# LowPassFilter.net
KiCad netlist of a schematic drawn in Altium Designer
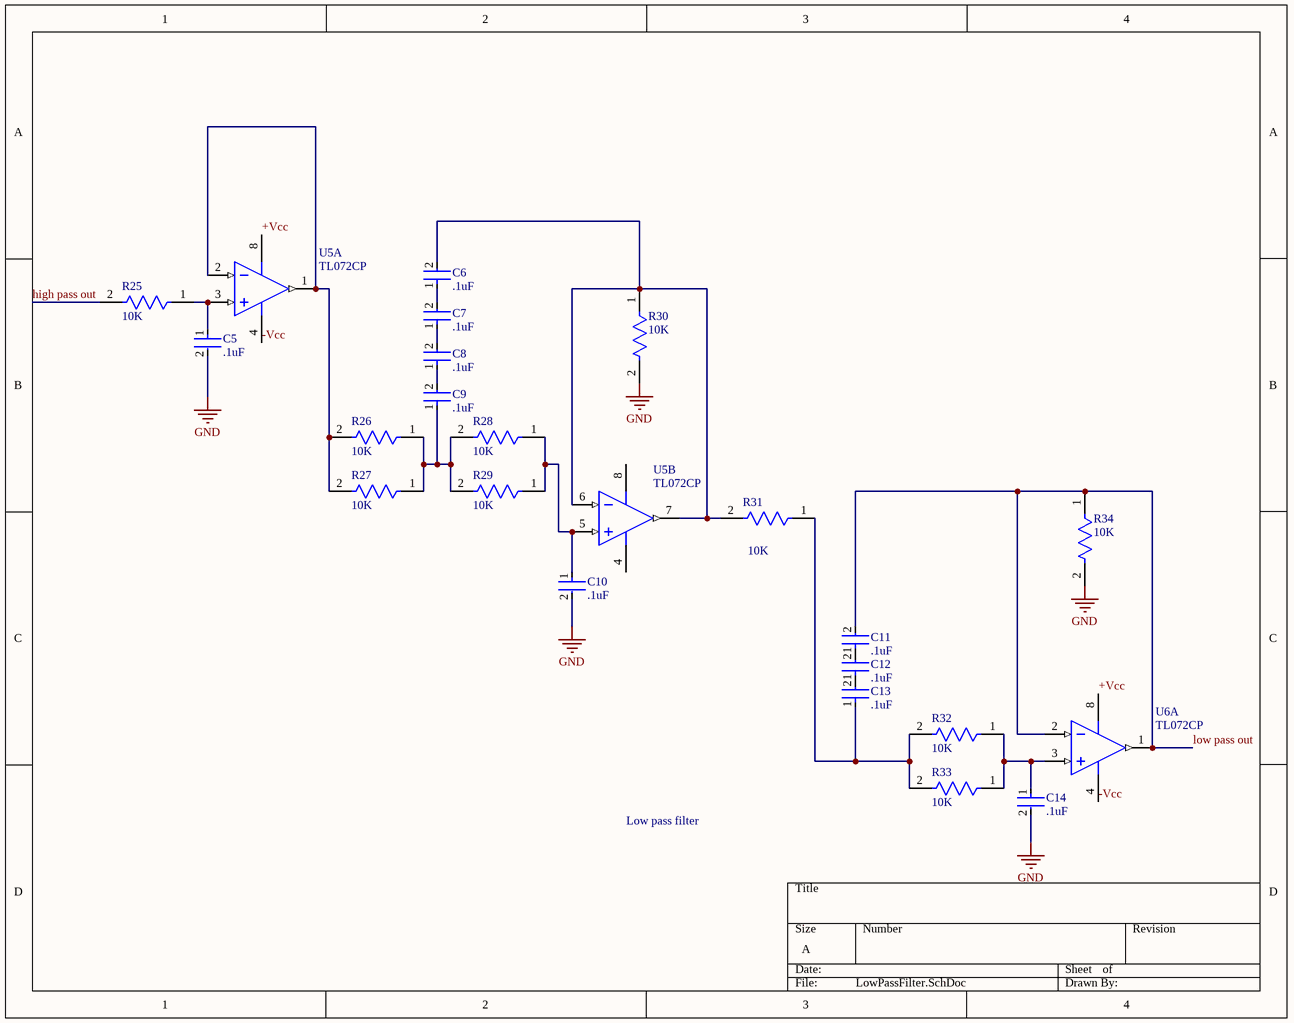
[diagram p0: LowPassFilter.SchDoc]

(export (version "E")
  (design (tool "Eeschema 10.0.6"))
  (components
    (comp (ref "C5")
      (value ".1uF")
      (footprint "FP-K15H5-MFG")
      (description "CAP CER 0.1UF 50V X7R RADIAL")
      (fields (field (name "VOLTAGE") "50V") (field (name "TOLERANCE") "10%"))
      (libsource (lib "Altium Content Vault") (part "11868f565c42a9108669ba33697ecf6"))
    )
    (comp (ref "C6")
      (value ".1uF")
      (footprint "FP-K15H5-MFG")
      (description "CAP CER 0.1UF 50V X7R RADIAL")
      (fields (field (name "VOLTAGE") "50V") (field (name "TOLERANCE") "10%"))
      (libsource (lib "Altium Content Vault") (part "11868f565c42a9108669ba33697ecf6"))
    )
    (comp (ref "C7")
      (value ".1uF")
      (footprint "FP-K15H5-MFG")
      (description "CAP CER 0.1UF 50V X7R RADIAL")
      (fields (field (name "VOLTAGE") "50V") (field (name "TOLERANCE") "10%"))
      (libsource (lib "Altium Content Vault") (part "11868f565c42a9108669ba33697ecf6"))
    )
    (comp (ref "C8")
      (value ".1uF")
      (footprint "FP-K15H5-MFG")
      (description "CAP CER 0.1UF 50V X7R RADIAL")
      (fields (field (name "VOLTAGE") "50V") (field (name "TOLERANCE") "10%"))
      (libsource (lib "Altium Content Vault") (part "11868f565c42a9108669ba33697ecf6"))
    )
    (comp (ref "C9")
      (value ".1uF")
      (footprint "FP-K15H5-MFG")
      (description "CAP CER 0.1UF 50V X7R RADIAL")
      (fields (field (name "VOLTAGE") "50V") (field (name "TOLERANCE") "10%"))
      (libsource (lib "Altium Content Vault") (part "11868f565c42a9108669ba33697ecf6"))
    )
    (comp (ref "C10")
      (value ".1uF")
      (footprint "FP-K15H5-MFG")
      (description "CAP CER 0.1UF 50V X7R RADIAL")
      (fields (field (name "VOLTAGE") "50V") (field (name "TOLERANCE") "10%"))
      (libsource (lib "Altium Content Vault") (part "11868f565c42a9108669ba33697ecf6"))
    )
    (comp (ref "C11")
      (value ".1uF")
      (footprint "FP-K15H5-MFG")
      (description "CAP CER 0.1UF 50V X7R RADIAL")
      (fields (field (name "VOLTAGE") "50V") (field (name "TOLERANCE") "10%"))
      (libsource (lib "Altium Content Vault") (part "11868f565c42a9108669ba33697ecf6"))
    )
    (comp (ref "C12")
      (value ".1uF")
      (footprint "FP-K15H5-MFG")
      (description "CAP CER 0.1UF 50V X7R RADIAL")
      (fields (field (name "VOLTAGE") "50V") (field (name "TOLERANCE") "10%"))
      (libsource (lib "Altium Content Vault") (part "11868f565c42a9108669ba33697ecf6"))
    )
    (comp (ref "C13")
      (value ".1uF")
      (footprint "FP-K15H5-MFG")
      (description "CAP CER 0.1UF 50V X7R RADIAL")
      (fields (field (name "VOLTAGE") "50V") (field (name "TOLERANCE") "10%"))
      (libsource (lib "Altium Content Vault") (part "11868f565c42a9108669ba33697ecf6"))
    )
    (comp (ref "C14")
      (value ".1uF")
      (footprint "FP-K15H5-MFG")
      (description "CAP CER 0.1UF 50V X7R RADIAL")
      (fields (field (name "VOLTAGE") "50V") (field (name "TOLERANCE") "10%"))
      (libsource (lib "Altium Content Vault") (part "11868f565c42a9108669ba33697ecf6"))
    )
    (comp (ref "R25")
      (value "10K")
      (footprint "FP-CFR-25-MFG")
      (description "RES 10 OHM 1/4W 5% AXIAL")
      (fields (field (name "TOLERANCE") "5%"))
      (libsource (lib "Altium Content Vault") (part "1029c3af85768c4190bb7ad29bc67b5"))
    )
    (comp (ref "R26")
      (value "10K")
      (footprint "FP-CFR-25-MFG")
      (description "RES 10 OHM 1/4W 5% AXIAL")
      (fields (field (name "TOLERANCE") "5%"))
      (libsource (lib "Altium Content Vault") (part "1029c3af85768c4190bb7ad29bc67b5"))
    )
    (comp (ref "R27")
      (value "10K")
      (footprint "FP-CFR-25-MFG")
      (description "RES 10 OHM 1/4W 5% AXIAL")
      (fields (field (name "TOLERANCE") "5%"))
      (libsource (lib "Altium Content Vault") (part "1029c3af85768c4190bb7ad29bc67b5"))
    )
    (comp (ref "R28")
      (value "10K")
      (footprint "FP-CFR-25-MFG")
      (description "RES 10 OHM 1/4W 5% AXIAL")
      (fields (field (name "TOLERANCE") "5%"))
      (libsource (lib "Altium Content Vault") (part "1029c3af85768c4190bb7ad29bc67b5"))
    )
    (comp (ref "R29")
      (value "10K")
      (footprint "FP-CFR-25-MFG")
      (description "RES 10 OHM 1/4W 5% AXIAL")
      (fields (field (name "TOLERANCE") "5%"))
      (libsource (lib "Altium Content Vault") (part "1029c3af85768c4190bb7ad29bc67b5"))
    )
    (comp (ref "R30")
      (value "10K")
      (footprint "FP-CFR-25-MFG")
      (description "RES 10 OHM 1/4W 5% AXIAL")
      (fields (field (name "TOLERANCE") "5%"))
      (libsource (lib "Altium Content Vault") (part "1029c3af85768c4190bb7ad29bc67b5"))
    )
    (comp (ref "R31")
      (value "10K")
      (footprint "FP-CFR-25-MFG")
      (description "RES 10 OHM 1/4W 5% AXIAL")
      (fields (field (name "TOLERANCE") "5%"))
      (libsource (lib "Altium Content Vault") (part "1029c3af85768c4190bb7ad29bc67b5"))
    )
    (comp (ref "R32")
      (value "10K")
      (footprint "FP-CFR-25-MFG")
      (description "RES 10 OHM 1/4W 5% AXIAL")
      (fields (field (name "TOLERANCE") "5%"))
      (libsource (lib "Altium Content Vault") (part "1029c3af85768c4190bb7ad29bc67b5"))
    )
    (comp (ref "R33")
      (value "10K")
      (footprint "FP-CFR-25-MFG")
      (description "RES 10 OHM 1/4W 5% AXIAL")
      (fields (field (name "TOLERANCE") "5%"))
      (libsource (lib "Altium Content Vault") (part "1029c3af85768c4190bb7ad29bc67b5"))
    )
    (comp (ref "R34")
      (value "10K")
      (footprint "FP-CFR-25-MFG")
      (description "RES 10 OHM 1/4W 5% AXIAL")
      (fields (field (name "TOLERANCE") "5%"))
      (libsource (lib "Altium Content Vault") (part "1029c3af85768c4190bb7ad29bc67b5"))
    )
    (comp (ref "U5")
      (value "TL072CP")
      (footprint "P0008A")
      (fields (field (name "MANUFACTURER") "Texas Instruments"))
      (libsource (lib "Altium Content Vault") (part "TI-AMP-D6-2-8_D"))
    )
    (comp (ref "U6")
      (value "TL072CP")
      (footprint "P0008A")
      (fields (field (name "MANUFACTURER") "Texas Instruments"))
      (libsource (lib "Altium Content Vault") (part "TI-AMP-D6-2-8_D"))
    )
  )
  (nets
    (net (code "1") (name "/+Vcc") (class "Default")
      (node (ref "U5") (pin "8") (pinfunction "VCC+_8") (pintype "power_in"))
      (node (ref "U6") (pin "8") (pinfunction "VCC+_8") (pintype "power_in"))
    )
    (net (code "2") (name "/-Vcc") (class "Default")
      (node (ref "U5") (pin "4") (pinfunction "VCC-_4") (pintype "power_in"))
      (node (ref "U6") (pin "4") (pinfunction "VCC-_4") (pintype "power_in"))
    )
    (net (code "3") (name "/high pass out") (class "Default")
      (node (ref "R25") (pin "2") (pinfunction "2_2") (pintype "passive"))
    )
    (net (code "4") (name "/low pass out") (class "Default")
      (node (ref "C11") (pin "2") (pinfunction "2_2") (pintype "passive"))
      (node (ref "R34") (pin "1") (pinfunction "1_1") (pintype "passive"))
      (node (ref "U6") (pin "1") (pinfunction "OUT1_1") (pintype "output"))
      (node (ref "U6") (pin "2") (pinfunction "IN1-_2") (pintype "input"))
    )
    (net (code "5") (name "GND") (class "Default")
      (node (ref "C10") (pin "2") (pinfunction "2_2") (pintype "passive"))
      (node (ref "C14") (pin "2") (pinfunction "2_2") (pintype "passive"))
      (node (ref "C5") (pin "2") (pinfunction "2_2") (pintype "passive"))
      (node (ref "R30") (pin "2") (pinfunction "2_2") (pintype "passive"))
      (node (ref "R34") (pin "2") (pinfunction "2_2") (pintype "passive"))
    )
    (net (code "6") (name "Net-(C6-Pad1)") (class "Default")
      (node (ref "C6") (pin "1") (pinfunction "1_1") (pintype "passive"))
      (node (ref "C7") (pin "2") (pinfunction "2_2") (pintype "passive"))
    )
    (net (code "7") (name "Net-(C7-Pad1)") (class "Default")
      (node (ref "C7") (pin "1") (pinfunction "1_1") (pintype "passive"))
      (node (ref "C8") (pin "2") (pinfunction "2_2") (pintype "passive"))
    )
    (net (code "8") (name "Net-(C8-Pad1)") (class "Default")
      (node (ref "C8") (pin "1") (pinfunction "1_1") (pintype "passive"))
      (node (ref "C9") (pin "2") (pinfunction "2_2") (pintype "passive"))
    )
    (net (code "9") (name "Net-(C9-Pad1)") (class "Default")
      (node (ref "C9") (pin "1") (pinfunction "1_1") (pintype "passive"))
      (node (ref "R26") (pin "1") (pinfunction "1_1") (pintype "passive"))
      (node (ref "R27") (pin "1") (pinfunction "1_1") (pintype "passive"))
      (node (ref "R28") (pin "2") (pinfunction "2_2") (pintype "passive"))
      (node (ref "R29") (pin "2") (pinfunction "2_2") (pintype "passive"))
    )
    (net (code "10") (name "Net-(C11-Pad1)") (class "Default")
      (node (ref "C11") (pin "1") (pinfunction "1_1") (pintype "passive"))
      (node (ref "C12") (pin "2") (pinfunction "2_2") (pintype "passive"))
    )
    (net (code "11") (name "Net-(C12-Pad1)") (class "Default")
      (node (ref "C12") (pin "1") (pinfunction "1_1") (pintype "passive"))
      (node (ref "C13") (pin "2") (pinfunction "2_2") (pintype "passive"))
    )
    (net (code "12") (name "Net-(C13-Pad1)") (class "Default")
      (node (ref "C13") (pin "1") (pinfunction "1_1") (pintype "passive"))
      (node (ref "R31") (pin "1") (pinfunction "1_1") (pintype "passive"))
      (node (ref "R32") (pin "2") (pinfunction "2_2") (pintype "passive"))
      (node (ref "R33") (pin "2") (pinfunction "2_2") (pintype "passive"))
    )
    (net (code "13") (name "Net-(U5A-IN1+)") (class "Default")
      (node (ref "C5") (pin "1") (pinfunction "1_1") (pintype "passive"))
      (node (ref "R25") (pin "1") (pinfunction "1_1") (pintype "passive"))
      (node (ref "U5") (pin "3") (pinfunction "IN1+_3") (pintype "input"))
    )
    (net (code "14") (name "Net-(U5A-IN1-)") (class "Default")
      (node (ref "R26") (pin "2") (pinfunction "2_2") (pintype "passive"))
      (node (ref "R27") (pin "2") (pinfunction "2_2") (pintype "passive"))
      (node (ref "U5") (pin "1") (pinfunction "OUT1_1") (pintype "output"))
      (node (ref "U5") (pin "2") (pinfunction "IN1-_2") (pintype "input"))
    )
    (net (code "15") (name "Net-(U5B-IN2+)") (class "Default")
      (node (ref "C10") (pin "1") (pinfunction "1_1") (pintype "passive"))
      (node (ref "R28") (pin "1") (pinfunction "1_1") (pintype "passive"))
      (node (ref "R29") (pin "1") (pinfunction "1_1") (pintype "passive"))
      (node (ref "U5") (pin "5") (pinfunction "IN2+_5") (pintype "input"))
    )
    (net (code "16") (name "Net-(U5B-IN2-)") (class "Default")
      (node (ref "C6") (pin "2") (pinfunction "2_2") (pintype "passive"))
      (node (ref "R30") (pin "1") (pinfunction "1_1") (pintype "passive"))
      (node (ref "R31") (pin "2") (pinfunction "2_2") (pintype "passive"))
      (node (ref "U5") (pin "6") (pinfunction "IN2-_6") (pintype "input"))
      (node (ref "U5") (pin "7") (pinfunction "OUT2_7") (pintype "output"))
    )
    (net (code "17") (name "Net-(U6A-IN1+)") (class "Default")
      (node (ref "C14") (pin "1") (pinfunction "1_1") (pintype "passive"))
      (node (ref "R32") (pin "1") (pinfunction "1_1") (pintype "passive"))
      (node (ref "R33") (pin "1") (pinfunction "1_1") (pintype "passive"))
      (node (ref "U6") (pin "3") (pinfunction "IN1+_3") (pintype "input"))
    )
    (net (code "18") (name "unconnected-(U5B-VCC+-Pad8)") (class "Default")
      (node (ref "U5") (pin "8") (pinfunction "VCC+_8") (pintype "power_in"))
    )
    (net (code "19") (name "unconnected-(U5B-VCC--Pad4)") (class "Default")
      (node (ref "U5") (pin "4") (pinfunction "VCC-_4") (pintype "power_in"))
    )
  )
)
